# Power_Supply.net
KiCad netlist of a schematic drawn in Altium Designer
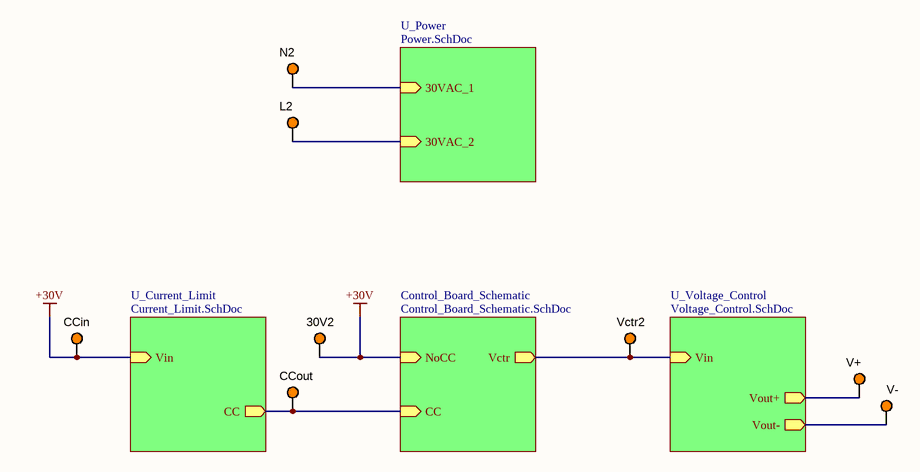
[diagram p0: Power_Supply.SchDoc]

(export (version "E")
  (design (tool "Eeschema 10.0.6"))
  (components
    (comp (ref "30V2")
      (value "5003")
      (footprint "KSTN-5003")
      (description "Test Point, Orange, Height 4.6 mm, Tail Length 3 mm, 1-Pin THD, RoHS")
      (fields (field (name "MANUFACTURER") "Keystone"))
      (libsource (lib "Konstantinos Psarras") (part "TESTPOINT_ORANGE"))
    )
    (comp (ref "CCin")
      (value "5003")
      (footprint "KSTN-5003")
      (description "Test Point, Orange, Height 4.6 mm, Tail Length 3 mm, 1-Pin THD, RoHS")
      (fields (field (name "MANUFACTURER") "Keystone"))
      (libsource (lib "Konstantinos Psarras") (part "TESTPOINT_ORANGE"))
    )
    (comp (ref "CCout")
      (value "5003")
      (footprint "KSTN-5003")
      (description "Test Point, Orange, Height 4.6 mm, Tail Length 3 mm, 1-Pin THD, RoHS")
      (fields (field (name "MANUFACTURER") "Keystone"))
      (libsource (lib "Konstantinos Psarras") (part "TESTPOINT_ORANGE"))
    )
    (comp (ref "L2")
      (value "5003")
      (footprint "KSTN-5003")
      (description "Test Point, Orange, Height 4.6 mm, Tail Length 3 mm, 1-Pin THD, RoHS")
      (fields (field (name "MANUFACTURER") "Keystone"))
      (libsource (lib "Konstantinos Psarras") (part "TESTPOINT_ORANGE"))
    )
    (comp (ref "N2")
      (value "5003")
      (footprint "KSTN-5003")
      (description "Test Point, Orange, Height 4.6 mm, Tail Length 3 mm, 1-Pin THD, RoHS")
      (fields (field (name "MANUFACTURER") "Keystone"))
      (libsource (lib "Konstantinos Psarras") (part "TESTPOINT_ORANGE"))
    )
    (comp (ref "V+")
      (value "5003")
      (footprint "KSTN-5003")
      (description "Test Point, Orange, Height 4.6 mm, Tail Length 3 mm, 1-Pin THD, RoHS")
      (fields (field (name "MANUFACTURER") "Keystone"))
      (libsource (lib "Konstantinos Psarras") (part "TESTPOINT_ORANGE"))
    )
    (comp (ref "V-")
      (value "5003")
      (footprint "KSTN-5003")
      (description "Test Point, Orange, Height 4.6 mm, Tail Length 3 mm, 1-Pin THD, RoHS")
      (fields (field (name "MANUFACTURER") "Keystone"))
      (libsource (lib "Konstantinos Psarras") (part "TESTPOINT_ORANGE"))
    )
    (comp (ref "Vctr2")
      (value "5003")
      (footprint "KSTN-5003")
      (description "Test Point, Orange, Height 4.6 mm, Tail Length 3 mm, 1-Pin THD, RoHS")
      (fields (field (name "MANUFACTURER") "Keystone"))
      (libsource (lib "Konstantinos Psarras") (part "TESTPOINT_ORANGE"))
    )
  )
  (nets
    (net (code "1") (name "+30V") (class "Default")
      (node (ref "30V2") (pin "1") (pinfunction "1_1") (pintype "passive"))
      (node (ref "CCin") (pin "1") (pinfunction "1_1") (pintype "passive"))
    )
    (net (code "2") (name "/30VAC_1") (class "Default")
      (node (ref "N2") (pin "1") (pinfunction "1_1") (pintype "passive"))
    )
    (net (code "3") (name "/30VAC_2") (class "Default")
      (node (ref "L2") (pin "1") (pinfunction "1_1") (pintype "passive"))
    )
    (net (code "4") (name "/CC") (class "Default")
      (node (ref "CCout") (pin "1") (pinfunction "1_1") (pintype "passive"))
    )
    (net (code "5") (name "/Vctr") (class "Default")
      (node (ref "Vctr2") (pin "1") (pinfunction "1_1") (pintype "passive"))
    )
    (net (code "6") (name "/Vout+") (class "Default")
      (node (ref "V+") (pin "1") (pinfunction "1_1") (pintype "passive"))
    )
    (net (code "7") (name "/Vout-") (class "Default")
      (node (ref "V-") (pin "1") (pinfunction "1_1") (pintype "passive"))
    )
  )
)
